# INA226_Current_Sensor.net
KiCad netlist of a schematic drawn in Altium Designer
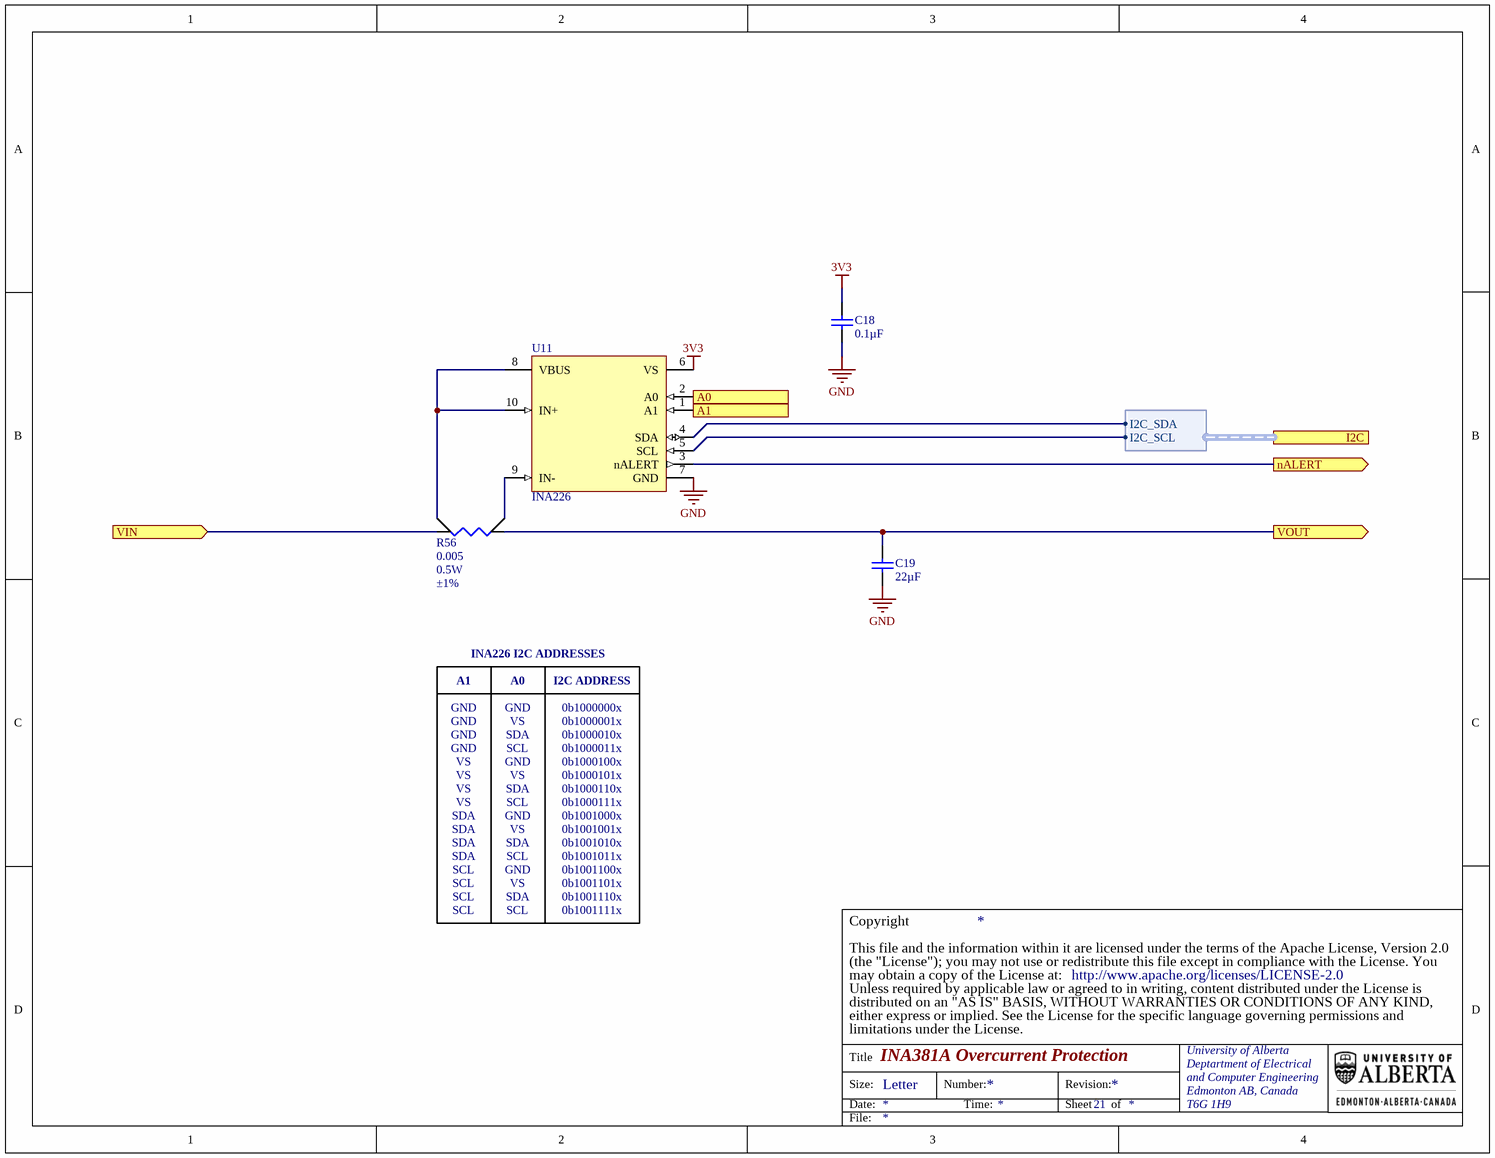
[diagram p0: INA226 Current Sensor.SchDoc]

(export (version "E")
  (design (tool "Eeschema 10.0.6"))
  (components
    (comp (ref "C18")
      (value "0.1µF")
      (footprint "TDK-CGA2B")
      (description "CAP CER 0.1UF 50V X7R 0402")
      (fields
        (field (name "PART NUMBER") "PC-TDK-02259")
        (field (name "MANUFACTURER PART NUMBER") "CGA2B3X7R1H104K050BB")
        (field (name "PUBLISHER") "AlbertaSat")
      )
      (libsource (lib "Database") (part "Cap"))
    )
    (comp (ref "C19")
      (value "22µF")
      (footprint "TDK-C3225")
      (description "CAP CER 22UF 25V X7R 1210")
      (fields
        (field (name "PART NUMBER") "PC-TDK-02965")
        (field (name "MANUFACTURER PART NUMBER") "C3225X7R1E226M250AB")
        (field (name "PUBLISHER") "AlbertaSat")
      )
      (libsource (lib "Database") (part "Cap"))
    )
    (comp (ref "R56")
      (value "0.005")
      (footprint "BRN-CRF0805")
      (description "RES 0.005 OHM 1% 1/2W 0805")
      (fields
        (field (name "POWER - RATED") "0.5W")
        (field (name "TOLERANCE") "±1%")
        (field (name "PART NUMBER") "PR-BRN-00023")
        (field (name "MANUFACTURER PART NUMBER") "CRF0805-FZ-R005ELF")
        (field (name "PUBLISHER") "AlbertaSat")
      )
      (libsource (lib "Database") (part "Res Sense"))
    )
    (comp (ref "U11")
      (value "INA226")
      (footprint "TI-DGS")
      (description "IC MONITOR PWR/CURR BIDIR 10MSOP")
      (fields (field (name "PART NUMBER") "19") (field (name "MANUFACTURER PART NUMBER") "INA226AQDGSRQ1"))
      (libsource (lib "Database") (part "INA226AQ"))
    )
  )
  (nets
    (net (code "2") (name "/A0") (class "Default")
      (node (ref "U11") (pin "2") (pinfunction "A0_2") (pintype "input"))
    )
    (net (code "3") (name "/A1") (class "Default")
      (node (ref "U11") (pin "1") (pinfunction "A1_1") (pintype "input"))
    )
    (net (code "4") (name "/I2C_SCL") (class "Default")
      (node (ref "U11") (pin "5") (pinfunction "SCL_5") (pintype "input"))
    )
    (net (code "5") (name "/I2C_SDA") (class "Default")
      (node (ref "U11") (pin "4") (pinfunction "SDA_4") (pintype "bidirectional"))
    )
    (net (code "6") (name "/VIN") (class "Default")
      (node (ref "R56") (pin "2") (pinfunction "I2_2") (pintype "passive"))
    )
    (net (code "7") (name "/VOUT") (class "Default")
      (node (ref "C19") (pin "2") (pinfunction "2_2") (pintype "passive"))
      (node (ref "R56") (pin "1") (pinfunction "I1_1") (pintype "passive"))
    )
    (net (code "8") (name "/nALERT") (class "Default")
      (node (ref "U11") (pin "3") (pinfunction "nALERT_3") (pintype "output"))
    )
    (net (code "10") (name "3V3") (class "Default")
      (node (ref "C18") (pin "2") (pinfunction "2_2") (pintype "passive"))
      (node (ref "U11") (pin "6") (pinfunction "VS_6") (pintype "passive"))
    )
    (net (code "11") (name "GND") (class "Default")
      (node (ref "C18") (pin "1") (pinfunction "1_1") (pintype "passive"))
      (node (ref "C19") (pin "1") (pinfunction "1_1") (pintype "passive"))
      (node (ref "U11") (pin "7") (pinfunction "GND_7") (pintype "power_in"))
    )
    (net (code "12") (name "Net-(R56-S1)") (class "Default")
      (node (ref "R56") (pin "4") (pinfunction "S1_4") (pintype "passive"))
      (node (ref "U11") (pin "9") (pinfunction "IN-_9") (pintype "input"))
    )
    (net (code "13") (name "Net-(R56-S2)") (class "Default")
      (node (ref "R56") (pin "3") (pinfunction "S2_3") (pintype "passive"))
      (node (ref "U11") (pin "10") (pinfunction "IN+_10") (pintype "input"))
      (node (ref "U11") (pin "8") (pinfunction "VBUS_8") (pintype "power_in"))
    )
  )
)
